# NIR-Spec-Motherboard-SCH_SH2__02.net
KiCad netlist of a schematic drawn in Altium Designer
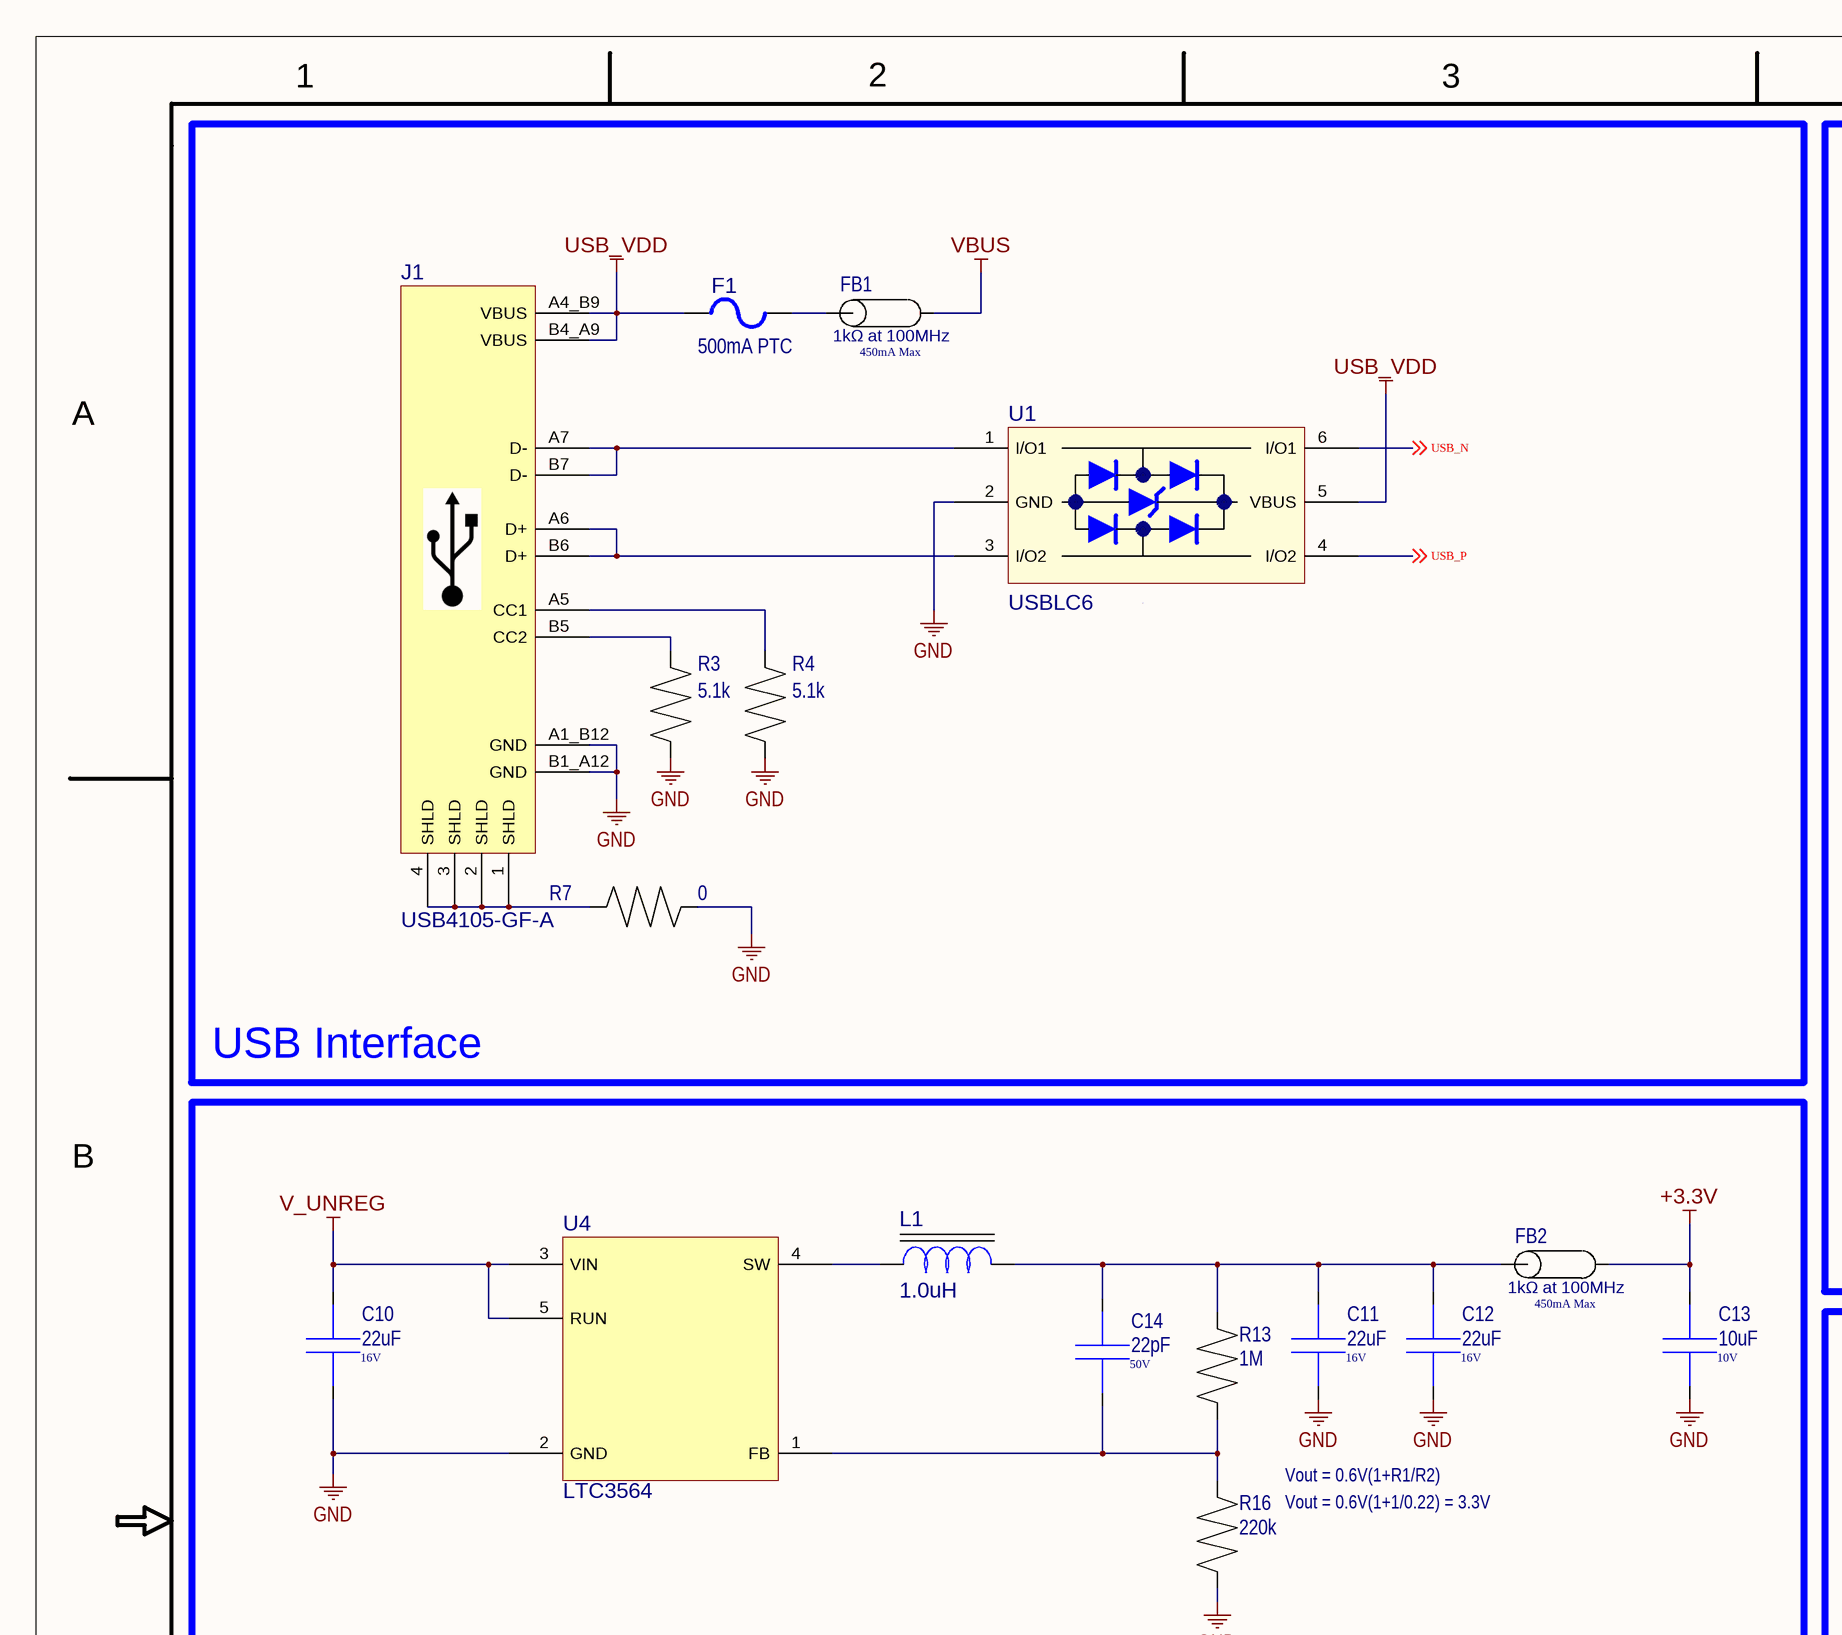
[diagram p0: NIR-Spec-Motherboard-SCH_SH2_(02).SchDoc, top left]
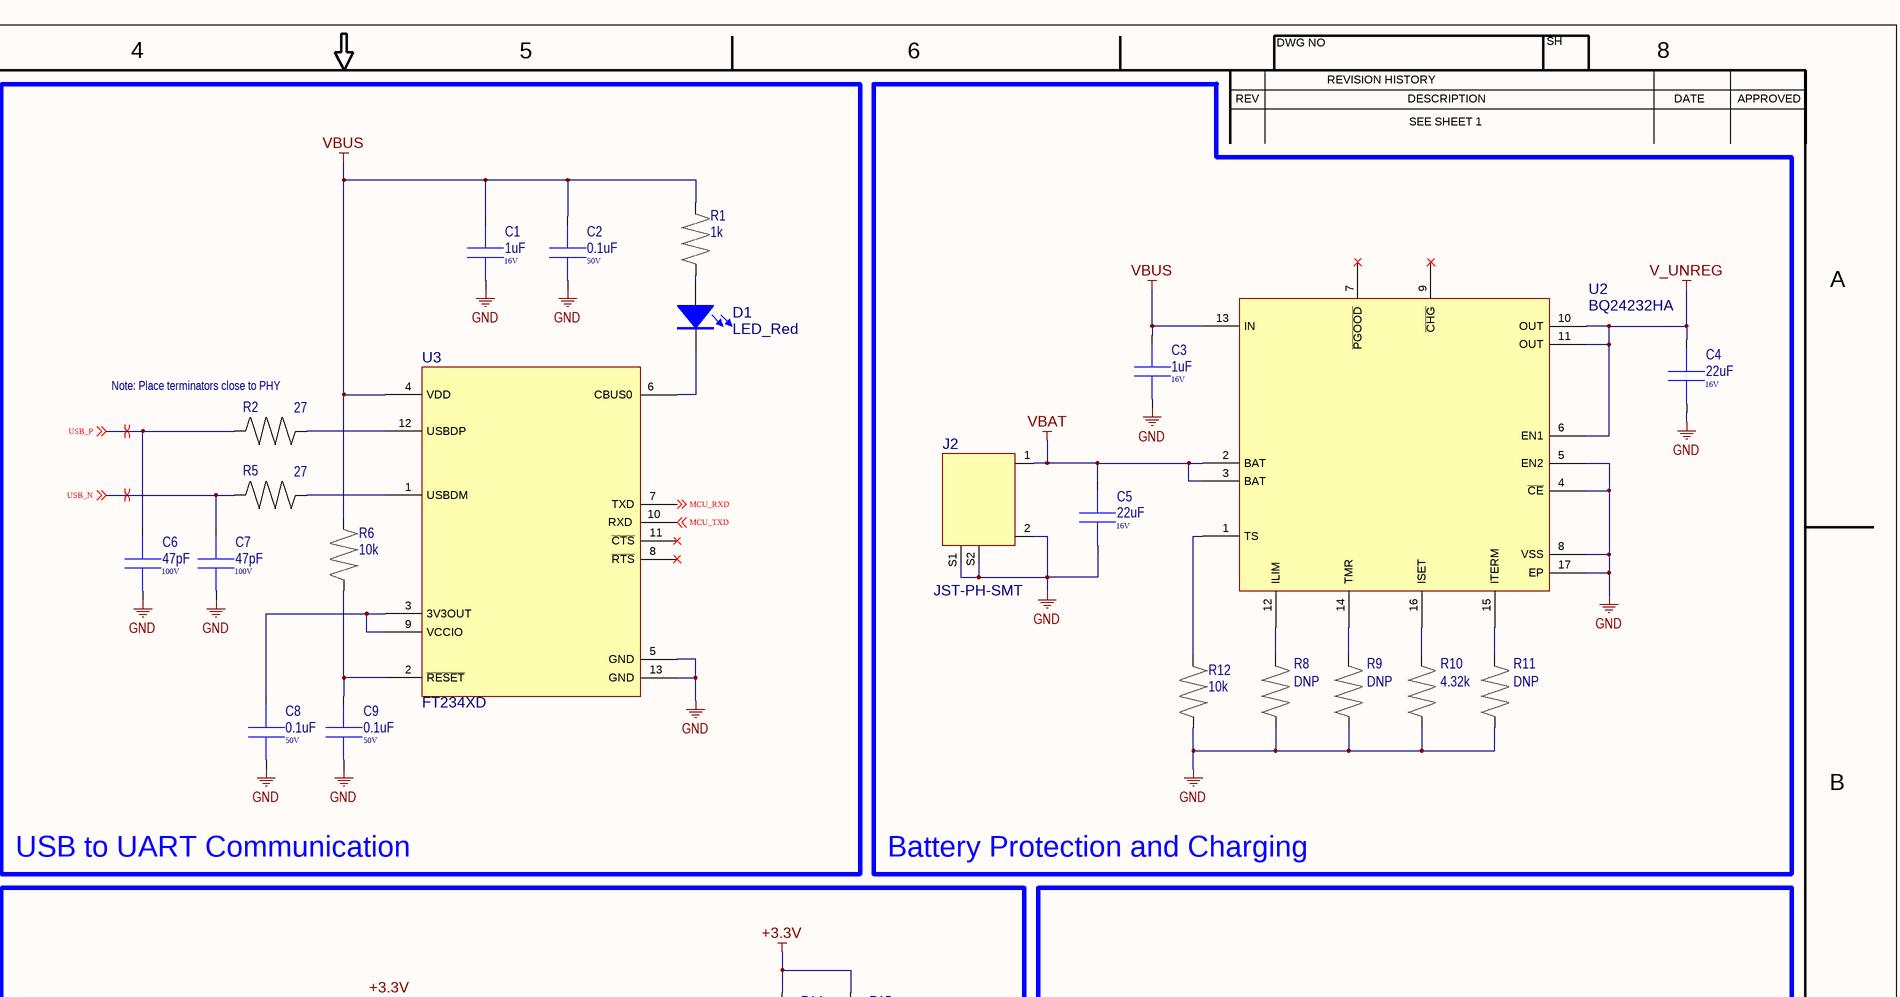
[diagram p1: NIR-Spec-Motherboard-SCH_SH2_(02).SchDoc, top right]
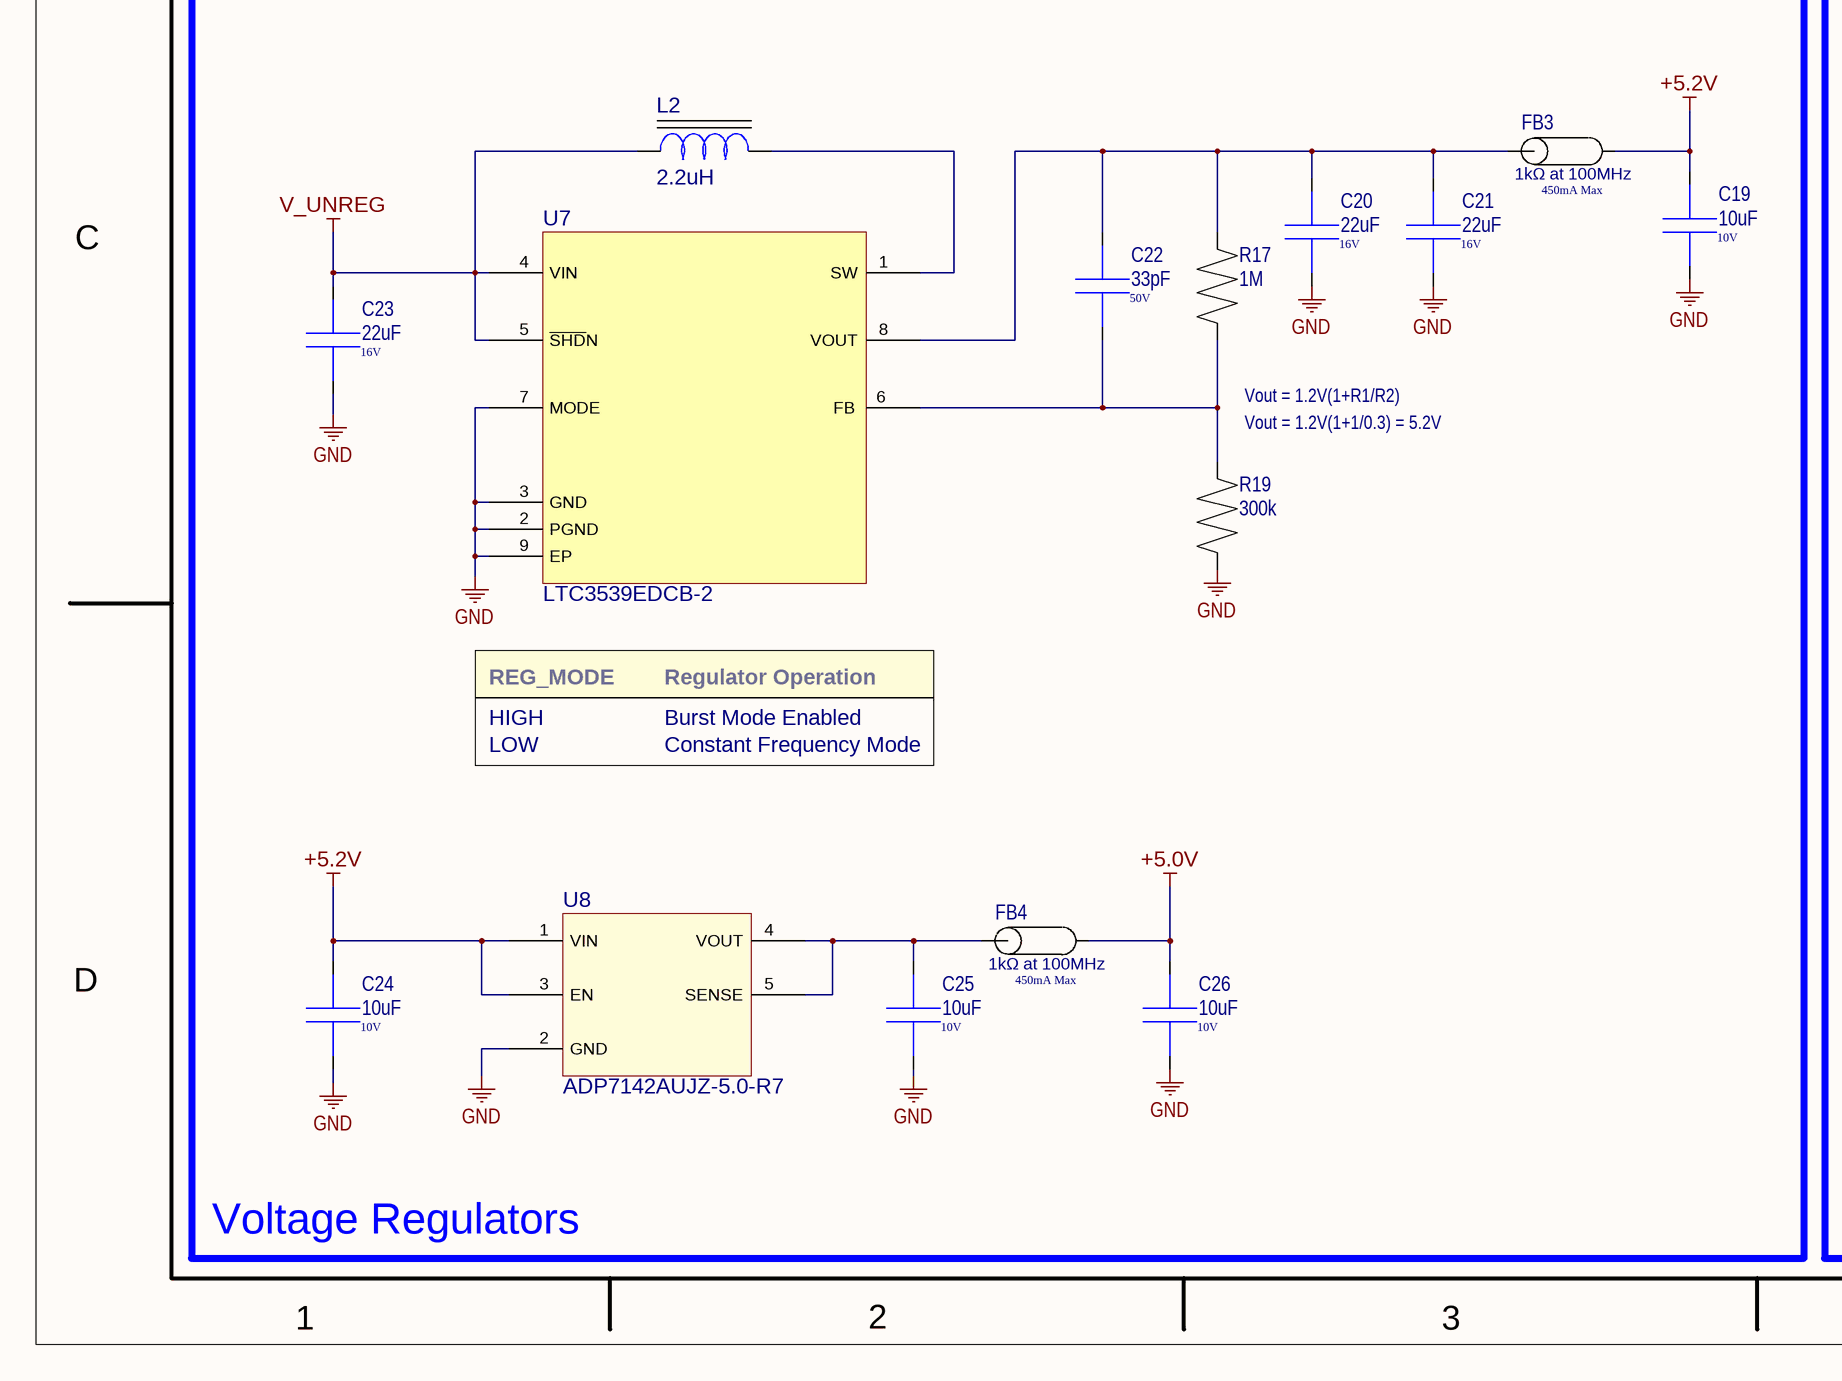
[diagram p2: NIR-Spec-Motherboard-SCH_SH2_(02).SchDoc, bottom left]
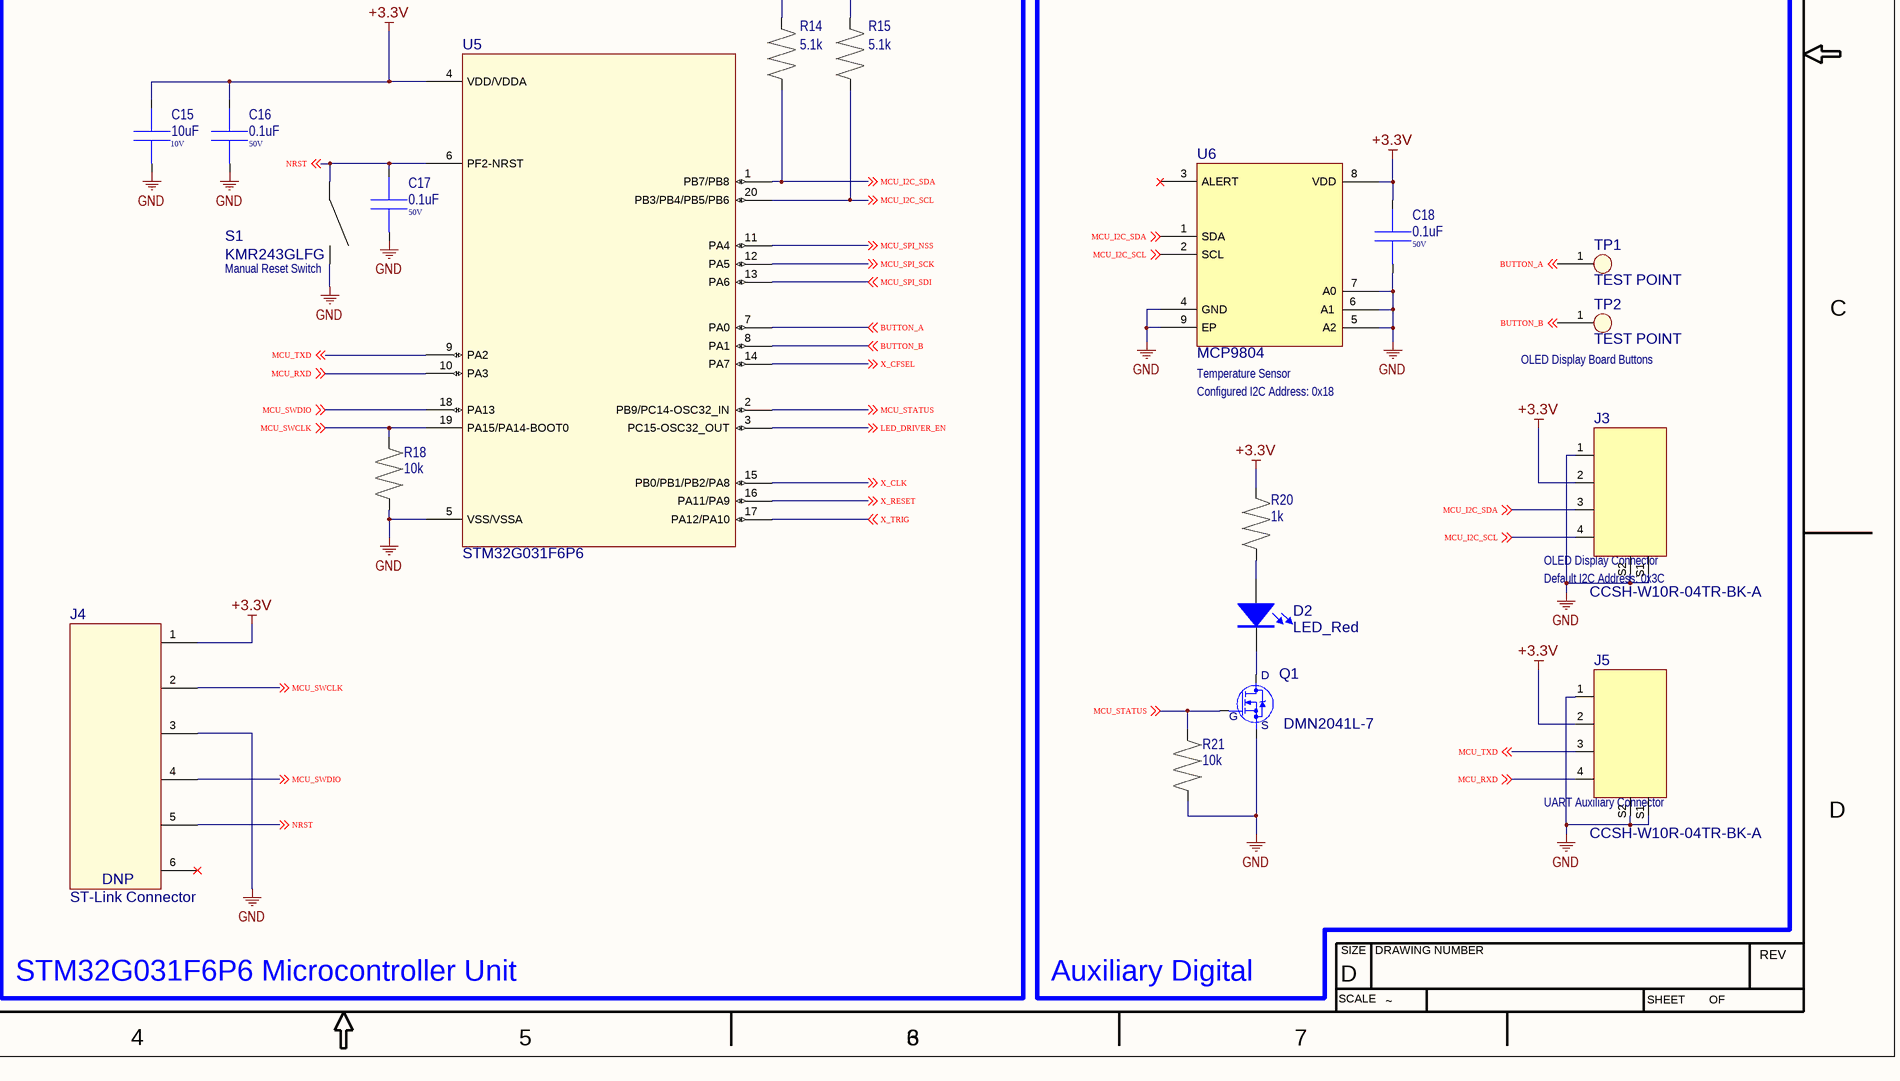
[diagram p3: NIR-Spec-Motherboard-SCH_SH2_(02).SchDoc, bottom right]

(export (version "E")
  (design (tool "Eeschema 10.0.6"))
  (components
    (comp (ref "C1")
      (value "1uF")
      (footprint "0603")
      (description "CAP CER 1UF 10V X5R 0603")
      (fields
        (field (name "PART NUMBER") "GRM188R61C105KA12J")
        (field (name "MANUFACTURER") "Murata Electronics")
        (field (name "VOLTAGE") "16V")
      )
      (libsource (lib "CAPACITORS") (part "CAP"))
    )
    (comp (ref "C2")
      (value "0.1uF")
      (footprint "0603")
      (description "CAP CER 0.1UF 50V X7R 0603")
      (fields
        (field (name "PART NUMBER") "C0603C104K5RAC3121")
        (field (name "MANUFACTURER") "KEMET")
        (field (name "VOLTAGE") "50V")
      )
      (libsource (lib "CAPACITORS") (part "CAP"))
    )
    (comp (ref "C3")
      (value "1uF")
      (footprint "0603")
      (description "CAP CER 1UF 10V X5R 0603")
      (fields
        (field (name "PART NUMBER") "GRM188R61C105KA12J")
        (field (name "MANUFACTURER") "Murata Electronics")
        (field (name "VOLTAGE") "16V")
      )
      (libsource (lib "CAPACITORS") (part "CAP"))
    )
    (comp (ref "C4")
      (value "22uF")
      (footprint "0805")
      (description "CAP CER 22UF 16V X5R 0805")
      (fields
        (field (name "PART NUMBER") "CL21A226MOCLRNC")
        (field (name "MANUFACTURER") "Samsung Electro-Mechanics")
        (field (name "VOLTAGE") "16V")
      )
      (libsource (lib "CAPACITORS") (part "CAP"))
    )
    (comp (ref "C5")
      (value "22uF")
      (footprint "0805")
      (description "CAP CER 22UF 16V X5R 0805")
      (fields
        (field (name "PART NUMBER") "CL21A226MOCLRNC")
        (field (name "MANUFACTURER") "Samsung Electro-Mechanics")
        (field (name "VOLTAGE") "16V")
      )
      (libsource (lib "CAPACITORS") (part "CAP"))
    )
    (comp (ref "C6")
      (value "47pF")
      (footprint "0603")
      (description "CAP CER 10PF 50V NP0 0603")
      (fields
        (field (name "PART NUMBER") "06031A470KAT2A")
        (field (name "MANUFACTURER") "Kyocera AVX")
        (field (name "VOLTAGE") "100V")
      )
      (libsource (lib "CAPACITORS") (part "CAP"))
    )
    (comp (ref "C7")
      (value "47pF")
      (footprint "0603")
      (description "CAP CER 10PF 50V NP0 0603")
      (fields
        (field (name "PART NUMBER") "06031A470KAT2A")
        (field (name "MANUFACTURER") "Kyocera AVX")
        (field (name "VOLTAGE") "100V")
      )
      (libsource (lib "CAPACITORS") (part "CAP"))
    )
    (comp (ref "C8")
      (value "0.1uF")
      (footprint "0603")
      (description "CAP CER 0.1UF 50V X7R 0603")
      (fields
        (field (name "PART NUMBER") "C0603C104K5RAC3121")
        (field (name "MANUFACTURER") "KEMET")
        (field (name "VOLTAGE") "50V")
      )
      (libsource (lib "CAPACITORS") (part "CAP"))
    )
    (comp (ref "C9")
      (value "0.1uF")
      (footprint "0603")
      (description "CAP CER 0.1UF 50V X7R 0603")
      (fields
        (field (name "PART NUMBER") "C0603C104K5RAC3121")
        (field (name "MANUFACTURER") "KEMET")
        (field (name "VOLTAGE") "50V")
      )
      (libsource (lib "CAPACITORS") (part "CAP"))
    )
    (comp (ref "C10")
      (value "22uF")
      (footprint "0805")
      (description "CAP CER 22UF 16V X5R 0805")
      (fields
        (field (name "PART NUMBER") "CL21A226MOCLRNC")
        (field (name "MANUFACTURER") "Samsung Electro-Mechanics")
        (field (name "VOLTAGE") "16V")
      )
      (libsource (lib "CAPACITORS") (part "CAP"))
    )
    (comp (ref "C11")
      (value "22uF")
      (footprint "0805")
      (description "CAP CER 22UF 16V X5R 0805")
      (fields
        (field (name "PART NUMBER") "CL21A226MOCLRNC")
        (field (name "MANUFACTURER") "Samsung Electro-Mechanics")
        (field (name "VOLTAGE") "16V")
      )
      (libsource (lib "CAPACITORS") (part "CAP"))
    )
    (comp (ref "C12")
      (value "22uF")
      (footprint "0805")
      (description "CAP CER 22UF 16V X5R 0805")
      (fields
        (field (name "PART NUMBER") "CL21A226MOCLRNC")
        (field (name "MANUFACTURER") "Samsung Electro-Mechanics")
        (field (name "VOLTAGE") "16V")
      )
      (libsource (lib "CAPACITORS") (part "CAP"))
    )
    (comp (ref "C13")
      (value "10uF")
      (footprint "0603")
      (description "CAP CER 10UF 10V X6S 0603")
      (fields
        (field (name "PART NUMBER") "GRM188C81A106MA73D")
        (field (name "MANUFACTURER") "Murata Electronics")
        (field (name "VOLTAGE") "10V")
      )
      (libsource (lib "CAPACITORS") (part "CAP"))
    )
    (comp (ref "C14")
      (value "22pF")
      (footprint "0603")
      (description "CAP CER 22PF NP0 50V 0603")
      (fields
        (field (name "PART NUMBER") "VJ0603A220KXAAC")
        (field (name "MANUFACTURER") "Vishay")
        (field (name "VOLTAGE") "50V")
      )
      (libsource (lib "CAPACITORS") (part "CAP"))
    )
    (comp (ref "C15")
      (value "10uF")
      (footprint "0603")
      (description "CAP CER 10UF 10V X6S 0603")
      (fields
        (field (name "PART NUMBER") "GRM188C81A106MA73D")
        (field (name "MANUFACTURER") "Murata Electronics")
        (field (name "VOLTAGE") "10V")
      )
      (libsource (lib "CAPACITORS") (part "CAP"))
    )
    (comp (ref "C16")
      (value "0.1uF")
      (footprint "0603")
      (description "CAP CER 0.1UF 50V X7R 0603")
      (fields
        (field (name "PART NUMBER") "C0603C104K5RAC3121")
        (field (name "MANUFACTURER") "KEMET")
        (field (name "VOLTAGE") "50V")
      )
      (libsource (lib "CAPACITORS") (part "CAP"))
    )
    (comp (ref "C17")
      (value "0.1uF")
      (footprint "0603")
      (description "CAP CER 0.1UF 50V X7R 0603")
      (fields
        (field (name "PART NUMBER") "C0603C104K5RAC3121")
        (field (name "MANUFACTURER") "KEMET")
        (field (name "VOLTAGE") "50V")
      )
      (libsource (lib "CAPACITORS") (part "CAP"))
    )
    (comp (ref "C18")
      (value "0.1uF")
      (footprint "0603")
      (description "CAP CER 0.1UF 50V X7R 0603")
      (fields
        (field (name "PART NUMBER") "C0603C104K5RAC3121")
        (field (name "MANUFACTURER") "KEMET")
        (field (name "VOLTAGE") "50V")
      )
      (libsource (lib "CAPACITORS") (part "CAP"))
    )
    (comp (ref "C19")
      (value "10uF")
      (footprint "0603")
      (description "CAP CER 10UF 10V X6S 0603")
      (fields
        (field (name "PART NUMBER") "GRM188C81A106MA73D")
        (field (name "MANUFACTURER") "Murata Electronics")
        (field (name "VOLTAGE") "10V")
      )
      (libsource (lib "CAPACITORS") (part "CAP"))
    )
    (comp (ref "C20")
      (value "22uF")
      (footprint "0805")
      (description "CAP CER 22UF 16V X5R 0805")
      (fields
        (field (name "PART NUMBER") "CL21A226MOCLRNC")
        (field (name "MANUFACTURER") "Samsung Electro-Mechanics")
        (field (name "VOLTAGE") "16V")
      )
      (libsource (lib "CAPACITORS") (part "CAP"))
    )
    (comp (ref "C21")
      (value "22uF")
      (footprint "0805")
      (description "CAP CER 22UF 16V X5R 0805")
      (fields
        (field (name "PART NUMBER") "CL21A226MOCLRNC")
        (field (name "MANUFACTURER") "Samsung Electro-Mechanics")
        (field (name "VOLTAGE") "16V")
      )
      (libsource (lib "CAPACITORS") (part "CAP"))
    )
    (comp (ref "C22")
      (value "33pF")
      (footprint "0603")
      (description "CAP CER 33PF 50V NP0 0603")
      (fields
        (field (name "PART NUMBER") "06035A330J4T4A")
        (field (name "MANUFACTURER") "Kyocera AVX")
        (field (name "VOLTAGE") "50V")
      )
      (libsource (lib "CAPACITORS") (part "CAP"))
    )
    (comp (ref "C23")
      (value "22uF")
      (footprint "0805")
      (description "CAP CER 22UF 16V X5R 0805")
      (fields
        (field (name "PART NUMBER") "CL21A226MOCLRNC")
        (field (name "MANUFACTURER") "Samsung Electro-Mechanics")
        (field (name "VOLTAGE") "16V")
      )
      (libsource (lib "CAPACITORS") (part "CAP"))
    )
    (comp (ref "C24")
      (value "10uF")
      (footprint "0603")
      (description "CAP CER 10UF 10V X6S 0603")
      (fields
        (field (name "PART NUMBER") "GRM188C81A106MA73D")
        (field (name "MANUFACTURER") "Murata Electronics")
        (field (name "VOLTAGE") "10V")
      )
      (libsource (lib "CAPACITORS") (part "CAP"))
    )
    (comp (ref "C25")
      (value "10uF")
      (footprint "0603")
      (description "CAP CER 10UF 10V X6S 0603")
      (fields
        (field (name "PART NUMBER") "GRM188C81A106MA73D")
        (field (name "MANUFACTURER") "Murata Electronics")
        (field (name "VOLTAGE") "10V")
      )
      (libsource (lib "CAPACITORS") (part "CAP"))
    )
    (comp (ref "C26")
      (value "10uF")
      (footprint "0603")
      (description "CAP CER 10UF 10V X6S 0603")
      (fields
        (field (name "PART NUMBER") "GRM188C81A106MA73D")
        (field (name "MANUFACTURER") "Murata Electronics")
        (field (name "VOLTAGE") "10V")
      )
      (libsource (lib "CAPACITORS") (part "CAP"))
    )
    (comp (ref "D1")
      (value "LED_Red")
      (footprint "0603_LED_Red")
      (description "Standard LEDs - SMD HE Red 645 nm Water Clear")
      (fields (field (name "PART NUMBER") "SM0603HCL") (field (name "MANUFACTURER") "Bivar"))
      (libsource (lib "SEMICONDUCTORS") (part "LED_Red"))
    )
    (comp (ref "D2")
      (value "LED_Red")
      (footprint "0603_LED_Red")
      (description "Standard LEDs - SMD HE Red 645 nm Water Clear")
      (fields (field (name "PART NUMBER") "SM0603HCL") (field (name "MANUFACTURER") "Bivar"))
      (libsource (lib "SEMICONDUCTORS") (part "LED_Red"))
    )
    (comp (ref "F1")
      (value "500mA PTC")
      (footprint "0603")
      (description "500mA PTC Fuse")
      (fields (field (name "PART NUMBER") "MF-FSMF050X-2") (field (name "MANUFACTURER") "Bourns"))
      (libsource (lib "Power") (part "FUSE"))
    )
    (comp (ref "FB1")
      (value "Ferrite_Bead")
      (footprint "0603")
      (description "Ferrite Beads 1000 OHM 25%")
      (fields
        (field (name "MANUFACTURER") "Murata Electronics")
        (field (name "PART NUMBER") "BLM18AG102SH1D")
        (field (name "RATED CURRENT") "450mA Max")
        (field (name "IMPEDANCE") "1kΩ at 100MHz")
      )
      (libsource (lib "Ferrite_Beads") (part "Ferrite_Bead"))
    )
    (comp (ref "FB2")
      (value "Ferrite_Bead")
      (footprint "0603")
      (description "Ferrite Beads 1000 OHM 25%")
      (fields
        (field (name "MANUFACTURER") "Murata Electronics")
        (field (name "PART NUMBER") "BLM18AG102SH1D")
        (field (name "RATED CURRENT") "450mA Max")
        (field (name "IMPEDANCE") "1kΩ at 100MHz")
      )
      (libsource (lib "Ferrite_Beads") (part "Ferrite_Bead"))
    )
    (comp (ref "FB3")
      (value "Ferrite_Bead")
      (footprint "0603")
      (description "Ferrite Beads 1000 OHM 25%")
      (fields
        (field (name "MANUFACTURER") "Murata Electronics")
        (field (name "PART NUMBER") "BLM18AG102SH1D")
        (field (name "RATED CURRENT") "450mA Max")
        (field (name "IMPEDANCE") "1kΩ at 100MHz")
      )
      (libsource (lib "Ferrite_Beads") (part "Ferrite_Bead"))
    )
    (comp (ref "FB4")
      (value "Ferrite_Bead")
      (footprint "0603")
      (description "Ferrite Beads 1000 OHM 25%")
      (fields
        (field (name "MANUFACTURER") "Murata Electronics")
        (field (name "PART NUMBER") "BLM18AG102SH1D")
        (field (name "RATED CURRENT") "450mA Max")
        (field (name "IMPEDANCE") "1kΩ at 100MHz")
      )
      (libsource (lib "Ferrite_Beads") (part "Ferrite_Bead"))
    )
    (comp (ref "J1")
      (value "USB4105-GF-A")
      (footprint "USB4105-GF-A")
      (fields (field (name "MANUFACTURER") "GCT"))
      (libsource (lib "USB4105-GF-A") (part "USB4105-GF-A"))
    )
    (comp (ref "J2")
      (value "JST-PH-SMT")
      (footprint "JST-PH-SMT")
      (libsource (lib "JST-PH-SMT") (part "JST-PH-SMT"))
    )
    (comp (ref "J3")
      (value "CCSH-W10R-04TR-BK-A")
      (footprint "PCBComponent_1")
      (fields (field (name "MANUFACTURER") "JST"))
      (libsource (lib "CCSH-W10R-04TR-BK-A") (part "CCSH-W10R-04TR-BK-A"))
    )
    (comp (ref "J4")
      (value "DNP")
      (footprint "851-43-006-10-001000")
      (description "CONN, RECPT, 6 POS, 0.050\" (1.27MM) GOLD TH")
      (fields (field (name "MANUFACTURER") "Mill-max") (field (name "PART NUMBER") "851-43-006-10-001000"))
      (libsource (lib "Connectors") (part "851-43-006-10-001000"))
    )
    (comp (ref "J5")
      (value "CCSH-W10R-04TR-BK-A")
      (footprint "PCBComponent_1")
      (fields (field (name "MANUFACTURER") "JST"))
      (libsource (lib "CCSH-W10R-04TR-BK-A") (part "CCSH-W10R-04TR-BK-A"))
    )
    (comp (ref "L1")
      (value "1.0uH")
      (footprint "1206")
      (description "SHIELDED_INDUCTOR")
      (fields (field (name "PART NUMBER") "MLP2016S1R0MT0S1") (field (name "MANUFACTURER") "TDK"))
      (libsource (lib "INDUCTORS") (part "SHIELDED_INDUCTOR"))
    )
    (comp (ref "L2")
      (value "2.2uH")
      (footprint "1206")
      (description "SHIELDED_INDUCTOR")
      (fields (field (name "PART NUMBER") "MLP2016H2R2MT0S1") (field (name "MANUFACTURER") "TDK"))
      (libsource (lib "INDUCTORS") (part "SHIELDED_INDUCTOR"))
    )
    (comp (ref "Q1")
      (value "DMN2041L-7")
      (footprint "SOT-23-3")
      (description "MOSFET, N CH, 3-PIN")
      (fields (field (name "MANUFACTURER") "Diodes Incorporated"))
      (libsource (lib "SEMICONDUCTORS") (part "MOSFET_N"))
    )
    (comp (ref "R1")
      (value "1k")
      (footprint "0603")
      (description "Thin Film Resistors - SMD CPF A 0603 1K0 0.1% 25PPM")
      (fields (field (name "PART NUMBER") "CPF-A-0603B1K0E") (field (name "MANUFACTURER") "TE Connectivity"))
      (libsource (lib "RESISTORS") (part "RES"))
    )
    (comp (ref "R2")
      (value "27")
      (footprint "0603")
      (description "Thin Film Resistors - SMD 0603 27ohms 50ppm 0.5%")
      (fields (field (name "PART NUMBER") "ERA-3AHD270V") (field (name "MANUFACTURER") "Panasonic"))
      (libsource (lib "RESISTORS") (part "RES"))
    )
    (comp (ref "R3")
      (value "5.1k")
      (footprint "0603")
      (description "Thick Film Resistors - SMD 0603 5.1Kohm 5% High Voltage")
      (fields (field (name "PART NUMBER") "KTR03EZPJ512") (field (name "MANUFACTURER") "ROHM Semiconductor"))
      (libsource (lib "RESISTORS") (part "RES"))
    )
    (comp (ref "R4")
      (value "5.1k")
      (footprint "0603")
      (description "Thick Film Resistors - SMD 0603 5.1Kohm 5% High Voltage")
      (fields (field (name "PART NUMBER") "KTR03EZPJ512") (field (name "MANUFACTURER") "ROHM Semiconductor"))
      (libsource (lib "RESISTORS") (part "RES"))
    )
    (comp (ref "R5")
      (value "27")
      (footprint "0603")
      (description "Thin Film Resistors - SMD 0603 27ohms 50ppm 0.5%")
      (fields (field (name "PART NUMBER") "ERA-3AHD270V") (field (name "MANUFACTURER") "Panasonic"))
      (libsource (lib "RESISTORS") (part "RES"))
    )
    (comp (ref "R6")
      (value "10k")
      (footprint "0603")
      (description "Thick Film Resistors - SMD 1/5W 10Kohms 1% 100ppm")
      (fields (field (name "PART NUMBER") "RCC060310K0FKEA") (field (name "MANUFACTURER") "Vishay"))
      (libsource (lib "RESISTORS") (part "RES"))
    )
    (comp (ref "R7")
      (value "0")
      (footprint "0603")
      (description "SMD 0.33W Zero ohm Jumper High Power")
      (fields (field (name "PART NUMBER") "CRCW06030000Z0EAHP") (field (name "MANUFACTURER") "Vishay"))
      (libsource (lib "RESISTORS") (part "RES"))
    )
    (comp (ref "R8")
      (value "DNP")
      (footprint "0603")
      (description "RESISTOR")
      (libsource (lib "RESISTORS") (part "RES"))
    )
    (comp (ref "R9")
      (value "DNP")
      (footprint "0603")
      (description "RESISTOR")
      (libsource (lib "RESISTORS") (part "RES"))
    )
    (comp (ref "R10")
      (value "4.32k")
      (footprint "0603")
      (description "Thick Film Resistors - SMD 4.32K ohm 1%")
      (fields (field (name "PART NUMBER") "CR0603-FX-4321ELF") (field (name "MANUFACTURER") "Bourns"))
      (libsource (lib "RESISTORS") (part "RES"))
    )
    (comp (ref "R11")
      (value "DNP")
      (footprint "0603")
      (description "RESISTOR")
      (libsource (lib "RESISTORS") (part "RES"))
    )
    (comp (ref "R12")
      (value "10k")
      (footprint "0603")
      (description "Thick Film Resistors - SMD 1/5W 10Kohms 1% 100ppm")
      (fields (field (name "PART NUMBER") "RCC060310K0FKEA") (field (name "MANUFACTURER") "Vishay"))
      (libsource (lib "RESISTORS") (part "RES"))
    )
    (comp (ref "R13")
      (value "1M")
      (footprint "0603")
      (description "Thick Film Resistors - SMD 1M 1% 1/10W")
      (fields (field (name "PART NUMBER") "CR0603-FX-1004ELF") (field (name "MANUFACTURER") "Bourns"))
      (libsource (lib "RESISTORS") (part "RES"))
    )
    (comp (ref "R14")
      (value "5.1k")
      (footprint "0603")
      (description "Thick Film Resistors - SMD 0603 5.1Kohm 5% High Voltage")
      (fields (field (name "PART NUMBER") "KTR03EZPJ512") (field (name "MANUFACTURER") "ROHM Semiconductor"))
      (libsource (lib "RESISTORS") (part "RES"))
    )
    (comp (ref "R15")
      (value "5.1k")
      (footprint "0603")
      (description "Thick Film Resistors - SMD 0603 5.1Kohm 5% High Voltage")
      (fields (field (name "PART NUMBER") "KTR03EZPJ512") (field (name "MANUFACTURER") "ROHM Semiconductor"))
      (libsource (lib "RESISTORS") (part "RES"))
    )
    (comp (ref "R16")
      (value "220k")
      (footprint "0603")
      (description "Thick Film Resistors - SMD 0603 220Kohm 1% Anti Surge AEC-Q200")
      (fields (field (name "PART NUMBER") "SDR03EZPF2203") (field (name "MANUFACTURER") "ROHM Semiconductor"))
      (libsource (lib "RESISTORS") (part "RES"))
    )
    (comp (ref "R17")
      (value "1M")
      (footprint "0603")
      (description "Thick Film Resistors - SMD 1M 1% 1/10W")
      (fields (field (name "PART NUMBER") "CR0603-FX-1004ELF") (field (name "MANUFACTURER") "Bourns"))
      (libsource (lib "RESISTORS") (part "RES"))
    )
    (comp (ref "R18")
      (value "10k")
      (footprint "0603")
      (description "Thick Film Resistors - SMD 1/5W 10Kohms 1% 100ppm")
      (fields (field (name "PART NUMBER") "RCC060310K0FKEA") (field (name "MANUFACTURER") "Vishay"))
      (libsource (lib "RESISTORS") (part "RES"))
    )
    (comp (ref "R19")
      (value "300k")
      (footprint "0603")
      (description "Thick Film Resistors - SMD 0603 249Kohms 0.2W 1% AEC-Q200")
      (fields (field (name "PART NUMBER") "ERJ-P03F2493V") (field (name "MANUFACTURER") "Panasonic"))
      (libsource (lib "RESISTORS") (part "RES"))
    )
    (comp (ref "R20")
      (value "1k")
      (footprint "0603")
      (description "Thin Film Resistors - SMD CPF A 0603 1K0 0.1% 25PPM")
      (fields (field (name "PART NUMBER") "CPF-A-0603B1K0E") (field (name "MANUFACTURER") "TE Connectivity"))
      (libsource (lib "RESISTORS") (part "RES"))
    )
    (comp (ref "R21")
      (value "10k")
      (footprint "0603")
      (description "Thick Film Resistors - SMD 1/5W 10Kohms 1% 100ppm")
      (fields (field (name "PART NUMBER") "RCC060310K0FKEA") (field (name "MANUFACTURER") "Vishay"))
      (libsource (lib "RESISTORS") (part "RES"))
    )
    (comp (ref "S1")
      (value "KMR243GLFG")
      (footprint "KMR 2 Series")
      (description "Tactile Switch SPST-NO Top Actuated Surface Mount")
      (fields (field (name "MANUFACTURER") "C&K") (field (name "PART NUMBER") "KMR243GFLG"))
      (libsource (lib "KMR2 Series") (part "KMR 2 Series"))
    )
    (comp (ref "TP1")
      (value "TEST POINT")
      (footprint "30x40 TP")
      (libsource (lib "TestPoint") (part "TEST POINT"))
    )
    (comp (ref "TP2")
      (value "TEST POINT")
      (footprint "30x40 TP")
      (libsource (lib "TestPoint") (part "TEST POINT"))
    )
    (comp (ref "U1")
      (value "USBLC6")
      (footprint "SOT-23-6_N")
      (description "IC ESD PROTECTION LO CAP SOT23-6")
      (fields (field (name "PART NUMBER") "USBLC6-2SC6") (field (name "MANUFACTURER") "STMicroelectronics"))
      (libsource (lib "SEMICONDUCTORS") (part "USBLC6-2SC6"))
    )
    (comp (ref "U2")
      (value "BQ24232HA")
      (footprint "QFN-16")
      (description "IC BATT CHG LI-ION 1CELL 16QFN")
      (fields (field (name "MANUFACTURER") "Texas Instruments"))
      (libsource (lib "BQ24232HA") (part "BQ24232HA"))
    )
    (comp (ref "U3")
      (value "FT234XD")
      (footprint "DFN-12")
      (description "IC USB SERIAL BASIC UART 12DFN")
      (fields (field (name "PART NUMBER") "FT234XD-R") (field (name "MANUFACTURER") "FTDI"))
      (libsource (lib "FT234XD") (part "FT234XD"))
    )
    (comp (ref "U4")
      (value "LTC3564")
      (footprint "TSOT-23-5")
      (description "IC REG BUCK ADJ 1.25A TSOT23-5")
      (fields (field (name "MANUFACTURER") "Linear Technology") (field (name "PART NUMBER") "LTC3564ES5"))
      (libsource (lib "LTC3564") (part "LTC3564"))
    )
    (comp (ref "U5")
      (value "STM32G031F6P6")
      (footprint "TSSOP-20")
      (description "IC MCU 32BIT 32KB FLASH 20TSSOP")
      (fields (field (name "MANUFACTURER") "STMicroelectronics"))
      (libsource (lib "STM32G031Fxxx") (part "STM32G031F6P6"))
    )
    (comp (ref "U6")
      (value "MCP9804")
      (footprint "DFN-8")
      (description "SENSOR DIGITAL -40C-125C 8DFN")
      (fields
        (field (name "MANUFACTURER") "Microchip Technology")
        (field (name "PART NUMBER") "MCP9804T-E/MC")
      )
      (libsource (lib "MCP9804") (part "MCP9804"))
    )
    (comp (ref "U7")
      (value "LTC3539EDCB-2")
      (footprint "DFN-8 2x3")
      (description "IC REG BOOST ADJUSTABLE 2A 8DFN")
      (fields
        (field (name "PART NUMBER") "LTC3539EDCB-2#TRMPBF")
        (field (name "MANUFACTURER") "Analog Devices Inc.")
      )
      (libsource (lib "LTC3539") (part "LTC3539"))
    )
    (comp (ref "U8")
      (value "ADP7142AUJZ-5.0-R7")
      (footprint "TSOT-23-5")
      (fields (field (name "MANUFACTURER") "Analog Devices"))
      (libsource (lib "ADP7142AUJZ-3.3-R7") (part "ADP7142AUJZ-3.3-R7"))
    )
  )
  (nets
    (net (code "1") (name "+3.3V") (class "Default")
      (node (ref "C13") (pin "2") (pinfunction "2_2") (pintype "passive"))
      (node (ref "C15") (pin "2") (pinfunction "2_2") (pintype "passive"))
      (node (ref "C16") (pin "2") (pinfunction "2_2") (pintype "passive"))
      (node (ref "C18") (pin "2") (pinfunction "2_2") (pintype "passive"))
      (node (ref "FB2") (pin "2") (pinfunction "2_2") (pintype "passive"))
      (node (ref "J3") (pin "2") (pinfunction "2_2") (pintype "passive"))
      (node (ref "J4") (pin "1") (pinfunction "1_1") (pintype "passive"))
      (node (ref "J5") (pin "2") (pinfunction "2_2") (pintype "passive"))
      (node (ref "R14") (pin "2") (pinfunction "2_2") (pintype "passive"))
      (node (ref "R15") (pin "2") (pinfunction "2_2") (pintype "passive"))
      (node (ref "R20") (pin "2") (pinfunction "2_2") (pintype "passive"))
      (node (ref "U5") (pin "4") (pinfunction "VDD/VDDA_4") (pintype "power_in"))
      (node (ref "U6") (pin "8") (pinfunction "VDD_8") (pintype "passive"))
    )
    (net (code "2") (name "+5.0V") (class "Default")
      (node (ref "C26") (pin "2") (pinfunction "2_2") (pintype "passive"))
      (node (ref "FB4") (pin "2") (pinfunction "2_2") (pintype "passive"))
    )
    (net (code "3") (name "+5.2V") (class "Default")
      (node (ref "C19") (pin "2") (pinfunction "2_2") (pintype "passive"))
      (node (ref "C24") (pin "2") (pinfunction "2_2") (pintype "passive"))
      (node (ref "FB3") (pin "2") (pinfunction "2_2") (pintype "passive"))
      (node (ref "U8") (pin "1") (pinfunction "VIN_1") (pintype "passive"))
      (node (ref "U8") (pin "3") (pinfunction "EN_3") (pintype "passive"))
    )
    (net (code "4") (name "BUTTON_A") (class "Default")
      (node (ref "TP1") (pin "1") (pinfunction "1_1") (pintype "passive"))
      (node (ref "U5") (pin "7") (pinfunction "PA0_7") (pintype "bidirectional"))
    )
    (net (code "5") (name "BUTTON_B") (class "Default")
      (node (ref "TP2") (pin "1") (pinfunction "1_1") (pintype "passive"))
      (node (ref "U5") (pin "8") (pinfunction "PA1_8") (pintype "bidirectional"))
    )
    (net (code "6") (name "GND") (class "Default")
      (node (ref "C1") (pin "1") (pinfunction "1_1") (pintype "passive"))
      (node (ref "C10") (pin "1") (pinfunction "1_1") (pintype "passive"))
      (node (ref "C11") (pin "1") (pinfunction "1_1") (pintype "passive"))
      (node (ref "C12") (pin "1") (pinfunction "1_1") (pintype "passive"))
      (node (ref "C13") (pin "1") (pinfunction "1_1") (pintype "passive"))
      (node (ref "C15") (pin "1") (pinfunction "1_1") (pintype "passive"))
      (node (ref "C16") (pin "1") (pinfunction "1_1") (pintype "passive"))
      (node (ref "C17") (pin "1") (pinfunction "1_1") (pintype "passive"))
      (node (ref "C18") (pin "1") (pinfunction "1_1") (pintype "passive"))
      (node (ref "C19") (pin "1") (pinfunction "1_1") (pintype "passive"))
      (node (ref "C2") (pin "1") (pinfunction "1_1") (pintype "passive"))
      (node (ref "C20") (pin "1") (pinfunction "1_1") (pintype "passive"))
      (node (ref "C21") (pin "1") (pinfunction "1_1") (pintype "passive"))
      (node (ref "C23") (pin "1") (pinfunction "1_1") (pintype "passive"))
      (node (ref "C24") (pin "1") (pinfunction "1_1") (pintype "passive"))
      (node (ref "C25") (pin "1") (pinfunction "1_1") (pintype "passive"))
      (node (ref "C26") (pin "1") (pinfunction "1_1") (pintype "passive"))
      (node (ref "C3") (pin "1") (pinfunction "1_1") (pintype "passive"))
      (node (ref "C4") (pin "1") (pinfunction "1_1") (pintype "passive"))
      (node (ref "C5") (pin "1") (pinfunction "1_1") (pintype "passive"))
      (node (ref "C6") (pin "1") (pinfunction "1_1") (pintype "passive"))
      (node (ref "C7") (pin "1") (pinfunction "1_1") (pintype "passive"))
      (node (ref "C8") (pin "1") (pinfunction "1_1") (pintype "passive"))
      (node (ref "C9") (pin "1") (pinfunction "1_1") (pintype "passive"))
      (node (ref "J1") (pin "A1_B12") (pinfunction "GND_A1_B12") (pintype "passive"))
      (node (ref "J1") (pin "B1_A12") (pinfunction "GND_B1_A12") (pintype "passive"))
      (node (ref "J2") (pin "2") (pinfunction "2_2") (pintype "passive"))
      (node (ref "J2") (pin "S1") (pinfunction "S1_S1") (pintype "passive"))
      (node (ref "J2") (pin "S2") (pinfunction "S2_S2") (pintype "passive"))
      (node (ref "J3") (pin "1") (pinfunction "1_1") (pintype "passive"))
      (node (ref "J3") (pin "S1") (pinfunction "S1_S1") (pintype "passive"))
      (node (ref "J3") (pin "S2") (pinfunction "S2_S2") (pintype "passive"))
      (node (ref "J4") (pin "3") (pinfunction "3_3") (pintype "passive"))
      (node (ref "J5") (pin "1") (pinfunction "1_1") (pintype "passive"))
      (node (ref "J5") (pin "S1") (pinfunction "S1_S1") (pintype "passive"))
      (node (ref "J5") (pin "S2") (pinfunction "S2_S2") (pintype "passive"))
      (node (ref "Q1") (pin "3") (pinfunction "S_3") (pintype "passive"))
      (node (ref "R10") (pin "1") (pinfunction "1_1") (pintype "passive"))
      (node (ref "R11") (pin "1") (pinfunction "1_1") (pintype "passive"))
      (node (ref "R12") (pin "2") (pinfunction "2_2") (pintype "passive"))
      (node (ref "R16") (pin "2") (pinfunction "2_2") (pintype "passive"))
      (node (ref "R18") (pin "2") (pinfunction "2_2") (pintype "passive"))
      (node (ref "R19") (pin "2") (pinfunction "2_2") (pintype "passive"))
      (node (ref "R21") (pin "2") (pinfunction "2_2") (pintype "passive"))
      (node (ref "R3") (pin "1") (pinfunction "1_1") (pintype "passive"))
      (node (ref "R4") (pin "1") (pinfunction "1_1") (pintype "passive"))
      (node (ref "R7") (pin "1") (pinfunction "1_1") (pintype "passive"))
      (node (ref "R8") (pin "1") (pinfunction "1_1") (pintype "passive"))
      (node (ref "R9") (pin "1") (pinfunction "1_1") (pintype "passive"))
      (node (ref "S1") (pin "2") (pinfunction "2_2") (pintype "passive"))
      (node (ref "U1") (pin "2") (pinfunction "GND_2") (pintype "passive"))
      (node (ref "U2") (pin "17") (pinfunction "EP_17") (pintype "passive"))
      (node (ref "U2") (pin "4") (pinfunction "~{CE}_4") (pintype "passive"))
      (node (ref "U2") (pin "5") (pinfunction "EN2_5") (pintype "passive"))
      (node (ref "U2") (pin "8") (pinfunction "VSS_8") (pintype "passive"))
      (node (ref "U3") (pin "13") (pinfunction "GND_13") (pintype "passive"))
      (node (ref "U3") (pin "5") (pinfunction "GND_5") (pintype "passive"))
      (node (ref "U4") (pin "2") (pinfunction "GND_2") (pintype "passive"))
      (node (ref "U5") (pin "5") (pinfunction "VSS/VSSA_5") (pintype "power_in"))
      (node (ref "U6") (pin "4") (pinfunction "GND_4") (pintype "passive"))
      (node (ref "U6") (pin "5") (pinfunction "A2_5") (pintype "passive"))
      (node (ref "U6") (pin "6") (pinfunction "A1_6") (pintype "passive"))
      (node (ref "U6") (pin "7") (pinfunction "A0_7") (pintype "passive"))
      (node (ref "U6") (pin "9") (pinfunction "EP_9") (pintype "passive"))
      (node (ref "U7") (pin "2") (pinfunction "PGND_2") (pintype "passive"))
      (node (ref "U7") (pin "3") (pinfunction "GND_3") (pintype "passive"))
      (node (ref "U7") (pin "7") (pinfunction "MODE_7") (pintype "passive"))
      (node (ref "U7") (pin "9") (pinfunction "EP_9") (pintype "passive"))
      (node (ref "U8") (pin "2") (pinfunction "GND_2") (pintype "passive"))
    )
    (net (code "7") (name "LED_DRIVER_EN") (class "Default")
      (node (ref "U5") (pin "3") (pinfunction "PC15-OSC32_OUT_3") (pintype "bidirectional"))
    )
    (net (code "8") (name "MCU_I2C_SCL") (class "Default")
      (node (ref "J3") (pin "4") (pinfunction "4_4") (pintype "passive"))
      (node (ref "R15") (pin "1") (pinfunction "1_1") (pintype "passive"))
      (node (ref "U5") (pin "20") (pinfunction "PB3/PB4/PB5/PB6_20") (pintype "bidirectional"))
      (node (ref "U6") (pin "2") (pinfunction "SCL_2") (pintype "passive"))
    )
    (net (code "9") (name "MCU_I2C_SDA") (class "Default")
      (node (ref "J3") (pin "3") (pinfunction "3_3") (pintype "passive"))
      (node (ref "R14") (pin "1") (pinfunction "1_1") (pintype "passive"))
      (node (ref "U5") (pin "1") (pinfunction "PB7/PB8_1") (pintype "bidirectional"))
      (node (ref "U6") (pin "1") (pinfunction "SDA_1") (pintype "passive"))
    )
    (net (code "10") (name "MCU_RXD") (class "Default")
      (node (ref "J5") (pin "4") (pinfunction "4_4") (pintype "passive"))
      (node (ref "U3") (pin "7") (pinfunction "TXD_7") (pintype "passive"))
      (node (ref "U5") (pin "10") (pinfunction "PA3_10") (pintype "bidirectional"))
    )
    (net (code "11") (name "MCU_SPI_NSS") (class "Default")
      (node (ref "U5") (pin "11") (pinfunction "PA4_11") (pintype "bidirectional"))
    )
    (net (code "12") (name "MCU_SPI_SCK") (class "Default")
      (node (ref "U5") (pin "12") (pinfunction "PA5_12") (pintype "bidirectional"))
    )
    (net (code "13") (name "MCU_SPI_SDI") (class "Default")
      (node (ref "U5") (pin "13") (pinfunction "PA6_13") (pintype "bidirectional"))
    )
    (net (code "14") (name "MCU_STATUS") (class "Default")
      (node (ref "Q1") (pin "1") (pinfunction "G_1") (pintype "passive"))
      (node (ref "R21") (pin "1") (pinfunction "1_1") (pintype "passive"))
      (node (ref "U5") (pin "2") (pinfunction "PB9/PC14-OSC32_IN_2") (pintype "bidirectional"))
    )
    (net (code "15") (name "MCU_SWCLK") (class "Default")
      (node (ref "J4") (pin "2") (pinfunction "2_2") (pintype "passive"))
      (node (ref "R18") (pin "1") (pinfunction "1_1") (pintype "passive"))
      (node (ref "U5") (pin "19") (pinfunction "PA15/PA14-BOOT0_19") (pintype "passive"))
    )
    (net (code "16") (name "MCU_SWDIO") (class "Default")
      (node (ref "J4") (pin "4") (pinfunction "4_4") (pintype "passive"))
      (node (ref "U5") (pin "18") (pinfunction "PA13_18") (pintype "bidirectional"))
    )
    (net (code "17") (name "MCU_TXD") (class "Default")
      (node (ref "J5") (pin "3") (pinfunction "3_3") (pintype "passive"))
      (node (ref "U3") (pin "10") (pinfunction "RXD_10") (pintype "passive"))
      (node (ref "U5") (pin "9") (pinfunction "PA2_9") (pintype "bidirectional"))
    )
    (net (code "18") (name "NRST") (class "Default")
      (node (ref "C17") (pin "2") (pinfunction "2_2") (pintype "passive"))
      (node (ref "J4") (pin "5") (pinfunction "5_5") (pintype "passive"))
      (node (ref "S1") (pin "1") (pinfunction "1_1") (pintype "passive"))
      (node (ref "U5") (pin "6") (pinfunction "PF2-NRST_6") (pintype "passive"))
    )
    (net (code "19") (name "Net-(C11-Pad2)") (class "Default")
      (node (ref "C11") (pin "2") (pinfunction "2_2") (pintype "passive"))
      (node (ref "C12") (pin "2") (pinfunction "2_2") (pintype "passive"))
      (node (ref "C14") (pin "2") (pinfunction "2_2") (pintype "passive"))
      (node (ref "FB2") (pin "1") (pinfunction "1_1") (pintype "passive"))
      (node (ref "L1") (pin "2") (pinfunction "2_2") (pintype "passive"))
      (node (ref "R13") (pin "1") (pinfunction "1_1") (pintype "passive"))
    )
    (net (code "20") (name "Net-(D1-A)") (class "Default")
      (node (ref "D1") (pin "1") (pinfunction "A_1") (pintype "passive"))
      (node (ref "R1") (pin "1") (pinfunction "1_1") (pintype "passive"))
    )
    (net (code "21") (name "Net-(D1-K)") (class "Default")
      (node (ref "D1") (pin "2") (pinfunction "K_2") (pintype "passive"))
      (node (ref "U3") (pin "6") (pinfunction "CBUS0_6") (pintype "passive"))
    )
    (net (code "22") (name "Net-(D2-A)") (class "Default")
      (node (ref "D2") (pin "1") (pinfunction "A_1") (pintype "passive"))
      (node (ref "R20") (pin "1") (pinfunction "1_1") (pintype "passive"))
    )
    (net (code "23") (name "Net-(D2-K)") (class "Default")
      (node (ref "D2") (pin "2") (pinfunction "K_2") (pintype "passive"))
      (node (ref "Q1") (pin "2") (pinfunction "D_2") (pintype "passive"))
    )
    (net (code "24") (name "Net-(F1-Pad2)") (class "Default")
      (node (ref "F1") (pin "2") (pinfunction "2_2") (pintype "passive"))
      (node (ref "FB1") (pin "1") (pinfunction "1_1") (pintype "passive"))
    )
    (net (code "25") (name "Net-(J1-CC1)") (class "Default")
      (node (ref "J1") (pin "A5") (pinfunction "CC1_A5") (pintype "passive"))
      (node (ref "R4") (pin "2") (pinfunction "2_2") (pintype "passive"))
    )
    (net (code "26") (name "Net-(J1-CC2)") (class "Default")
      (node (ref "J1") (pin "B5") (pinfunction "CC2_B5") (pintype "passive"))
      (node (ref "R3") (pin "2") (pinfunction "2_2") (pintype "passive"))
    )
    (net (code "27") (name "Net-(J1-D+-PadA6)") (class "Default")
      (node (ref "J1") (pin "A6") (pinfunction "D+_A6") (pintype "passive"))
      (node (ref "J1") (pin "B6") (pinfunction "D+_B6") (pintype "passive"))
      (node (ref "U1") (pin "3") (pinfunction "I/O2_3") (pintype "passive"))
    )
    (net (code "28") (name "Net-(J1-D--PadA7)") (class "Default")
      (node (ref "J1") (pin "A7") (pinfunction "D-_A7") (pintype "passive"))
      (node (ref "J1") (pin "B7") (pinfunction "D-_B7") (pintype "passive"))
      (node (ref "U1") (pin "1") (pinfunction "I/O1_1") (pintype "passive"))
    )
    (net (code "29") (name "Net-(J1-SHLD-Pad1)") (class "Default")
      (node (ref "J1") (pin "1") (pinfunction "SHLD_1") (pintype "passive"))
      (node (ref "J1") (pin "2") (pinfunction "SHLD_2") (pintype "passive"))
      (node (ref "J1") (pin "3") (pinfunction "SHLD_3") (pintype "passive"))
      (node (ref "J1") (pin "4") (pinfunction "SHLD_4") (pintype "passive"))
      (node (ref "R7") (pin "2") (pinfunction "2_2") (pintype "passive"))
    )
    (net (code "30") (name "Net-(U2-ILIM)") (class "Default")
      (node (ref "R8") (pin "2") (pinfunction "2_2") (pintype "passive"))
      (node (ref "U2") (pin "12") (pinfunction "ILIM_12") (pintype "passive"))
    )
    (net (code "31") (name "Net-(U2-ISET)") (class "Default")
      (node (ref "R10") (pin "2") (pinfunction "2_2") (pintype "passive"))
      (node (ref "U2") (pin "16") (pinfunction "ISET_16") (pintype "passive"))
    )
    (net (code "32") (name "Net-(U2-ITERM)") (class "Default")
      (node (ref "R11") (pin "2") (pinfunction "2_2") (pintype "passive"))
      (node (ref "U2") (pin "15") (pinfunction "ITERM_15") (pintype "passive"))
    )
    (net (code "33") (name "Net-(U2-TMR)") (class "Default")
      (node (ref "R9") (pin "2") (pinfunction "2_2") (pintype "passive"))
      (node (ref "U2") (pin "14") (pinfunction "TMR_14") (pintype "passive"))
    )
    (net (code "34") (name "Net-(U2-TS)") (class "Default")
      (node (ref "R12") (pin "1") (pinfunction "1_1") (pintype "passive"))
      (node (ref "U2") (pin "1") (pinfunction "TS_1") (pintype "passive"))
    )
    (net (code "35") (name "Net-(U3-3V3OUT)") (class "Default")
      (node (ref "C8") (pin "2") (pinfunction "2_2") (pintype "passive"))
      (node (ref "U3") (pin "3") (pinfunction "3V3OUT_3") (pintype "passive"))
      (node (ref "U3") (pin "9") (pinfunction "VCCIO_9") (pintype "passive"))
    )
    (net (code "36") (name "Net-(U3-USBDM)") (class "Default")
      (node (ref "R5") (pin "2") (pinfunction "2_2") (pintype "passive"))
      (node (ref "U3") (pin "1") (pinfunction "USBDM_1") (pintype "passive"))
    )
    (net (code "37") (name "Net-(U3-USBDP)") (class "Default")
      (node (ref "R2") (pin "2") (pinfunction "2_2") (pintype "passive"))
      (node (ref "U3") (pin "12") (pinfunction "USBDP_12") (pintype "passive"))
    )
    (net (code "38") (name "Net-(U3-~{RESET})") (class "Default")
      (node (ref "C9") (pin "2") (pinfunction "2_2") (pintype "passive"))
      (node (ref "R6") (pin "2") (pinfunction "2_2") (pintype "passive"))
      (node (ref "U3") (pin "2") (pinfunction "~{RESET}_2") (pintype "passive"))
    )
    (net (code "39") (name "Net-(U4-FB)") (class "Default")
      (node (ref "C14") (pin "1") (pinfunction "1_1") (pintype "passive"))
      (node (ref "R13") (pin "2") (pinfunction "2_2") (pintype "passive"))
      (node (ref "R16") (pin "1") (pinfunction "1_1") (pintype "passive"))
      (node (ref "U4") (pin "1") (pinfunction "FB_1") (pintype "passive"))
    )
    (net (code "40") (name "Net-(U4-SW)") (class "Default")
      (node (ref "L1") (pin "1") (pinfunction "1_1") (pintype "passive"))
      (node (ref "U4") (pin "4") (pinfunction "SW_4") (pintype "passive"))
    )
    (net (code "41") (name "Net-(U7-FB)") (class "Default")
      (node (ref "C22") (pin "1") (pinfunction "1_1") (pintype "passive"))
      (node (ref "R17") (pin "2") (pinfunction "2_2") (pintype "passive"))
      (node (ref "R19") (pin "1") (pinfunction "1_1") (pintype "passive"))
      (node (ref "U7") (pin "6") (pinfunction "FB_6") (pintype "passive"))
    )
    (net (code "42") (name "Net-(U7-SW)") (class "Default")
      (node (ref "L2") (pin "2") (pinfunction "2_2") (pintype "passive"))
      (node (ref "U7") (pin "1") (pinfunction "SW_1") (pintype "passive"))
    )
    (net (code "43") (name "Net-(U7-VOUT)") (class "Default")
      (node (ref "C20") (pin "2") (pinfunction "2_2") (pintype "passive"))
      (node (ref "C21") (pin "2") (pinfunction "2_2") (pintype "passive"))
      (node (ref "C22") (pin "2") (pinfunction "2_2") (pintype "passive"))
      (node (ref "FB3") (pin "1") (pinfunction "1_1") (pintype "passive"))
      (node (ref "R17") (pin "1") (pinfunction "1_1") (pintype "passive"))
      (node (ref "U7") (pin "8") (pinfunction "VOUT_8") (pintype "passive"))
    )
    (net (code "44") (name "Net-(U8-SENSE)") (class "Default")
      (node (ref "C25") (pin "2") (pinfunction "2_2") (pintype "passive"))
      (node (ref "FB4") (pin "1") (pinfunction "1_1") (pintype "passive"))
      (node (ref "U8") (pin "4") (pinfunction "VOUT_4") (pintype "passive"))
      (node (ref "U8") (pin "5") (pinfunction "SENSE_5") (pintype "passive"))
    )
    (net (code "45") (name "USB_N") (class "Default")
      (node (ref "C7") (pin "2") (pinfunction "2_2") (pintype "passive"))
      (node (ref "R5") (pin "1") (pinfunction "1_1") (pintype "passive"))
      (node (ref "U1") (pin "6") (pinfunction "I/O1_6") (pintype "passive"))
    )
    (net (code "46") (name "USB_P") (class "Default")
      (node (ref "C6") (pin "2") (pinfunction "2_2") (pintype "passive"))
      (node (ref "R2") (pin "1") (pinfunction "1_1") (pintype "passive"))
      (node (ref "U1") (pin "4") (pinfunction "I/O2_4") (pintype "passive"))
    )
    (net (code "47") (name "USB_VDD") (class "Default")
      (node (ref "F1") (pin "1") (pinfunction "1_1") (pintype "passive"))
      (node (ref "J1") (pin "A4_B9") (pinfunction "VBUS_A4_B9") (pintype "passive"))
      (node (ref "J1") (pin "B4_A9") (pinfunction "VBUS_B4_A9") (pintype "passive"))
      (node (ref "U1") (pin "5") (pinfunction "VBUS_5") (pintype "passive"))
    )
    (net (code "48") (name "VBAT") (class "Default")
      (node (ref "C5") (pin "2") (pinfunction "2_2") (pintype "passive"))
      (node (ref "J2") (pin "1") (pinfunction "1_1") (pintype "passive"))
      (node (ref "U2") (pin "2") (pinfunction "BAT_2") (pintype "passive"))
      (node (ref "U2") (pin "3") (pinfunction "BAT_3") (pintype "passive"))
    )
    (net (code "49") (name "VBUS") (class "Default")
      (node (ref "C1") (pin "2") (pinfunction "2_2") (pintype "passive"))
      (node (ref "C2") (pin "2") (pinfunction "2_2") (pintype "passive"))
      (node (ref "C3") (pin "2") (pinfunction "2_2") (pintype "passive"))
      (node (ref "FB1") (pin "2") (pinfunction "2_2") (pintype "passive"))
      (node (ref "R1") (pin "2") (pinfunction "2_2") (pintype "passive"))
      (node (ref "R6") (pin "1") (pinfunction "1_1") (pintype "passive"))
      (node (ref "U2") (pin "13") (pinfunction "IN_13") (pintype "passive"))
      (node (ref "U3") (pin "4") (pinfunction "VDD_4") (pintype "passive"))
    )
    (net (code "50") (name "V_UNREG") (class "Default")
      (node (ref "C10") (pin "2") (pinfunction "2_2") (pintype "passive"))
      (node (ref "C23") (pin "2") (pinfunction "2_2") (pintype "passive"))
      (node (ref "C4") (pin "2") (pinfunction "2_2") (pintype "passive"))
      (node (ref "L2") (pin "1") (pinfunction "1_1") (pintype "passive"))
      (node (ref "U2") (pin "10") (pinfunction "OUT_10") (pintype "passive"))
      (node (ref "U2") (pin "11") (pinfunction "OUT_11") (pintype "passive"))
      (node (ref "U2") (pin "6") (pinfunction "EN1_6") (pintype "passive"))
      (node (ref "U4") (pin "3") (pinfunction "VIN_3") (pintype "passive"))
      (node (ref "U4") (pin "5") (pinfunction "RUN_5") (pintype "passive"))
      (node (ref "U7") (pin "4") (pinfunction "VIN_4") (pintype "passive"))
      (node (ref "U7") (pin "5") (pinfunction "~{SHD}N_5") (pintype "passive"))
    )
    (net (code "51") (name "X_CFSEL") (class "Default")
      (node (ref "U5") (pin "14") (pinfunction "PA7_14") (pintype "bidirectional"))
    )
    (net (code "52") (name "X_CLK") (class "Default")
      (node (ref "U5") (pin "15") (pinfunction "PB0/PB1/PB2/PA8_15") (pintype "bidirectional"))
    )
    (net (code "53") (name "X_RESET") (class "Default")
      (node (ref "U5") (pin "16") (pinfunction "PA11/PA9_16") (pintype "bidirectional"))
    )
    (net (code "54") (name "X_TRIG") (class "Default")
      (node (ref "U5") (pin "17") (pinfunction "PA12/PA10_17") (pintype "bidirectional"))
    )
    (net (code "55") (name "unconnected-(J4-Pad6)") (class "Default")
      (node (ref "J4") (pin "6") (pinfunction "6_6") (pintype "passive+no_connect"))
    )
    (net (code "56") (name "unconnected-(U2-~{CHG}-Pad9)") (class "Default")
      (node (ref "U2") (pin "9") (pinfunction "~{CHG}_9") (pintype "passive+no_connect"))
    )
    (net (code "57") (name "unconnected-(U2-~{PGOOD}-Pad7)") (class "Default")
      (node (ref "U2") (pin "7") (pinfunction "~{PGOOD}_7") (pintype "passive+no_connect"))
    )
    (net (code "58") (name "unconnected-(U3-~{CTS}-Pad11)") (class "Default")
      (node (ref "U3") (pin "11") (pinfunction "~{CTS}_11") (pintype "passive+no_connect"))
    )
    (net (code "59") (name "unconnected-(U3-~{RTS}-Pad8)") (class "Default")
      (node (ref "U3") (pin "8") (pinfunction "~{RTS}_8") (pintype "passive+no_connect"))
    )
    (net (code "60") (name "unconnected-(U6-ALERT-Pad3)") (class "Default")
      (node (ref "U6") (pin "3") (pinfunction "ALERT_3") (pintype "passive+no_connect"))
    )
  )
)
